# untitled.net
KiCad netlist of a schematic drawn in EAGLE
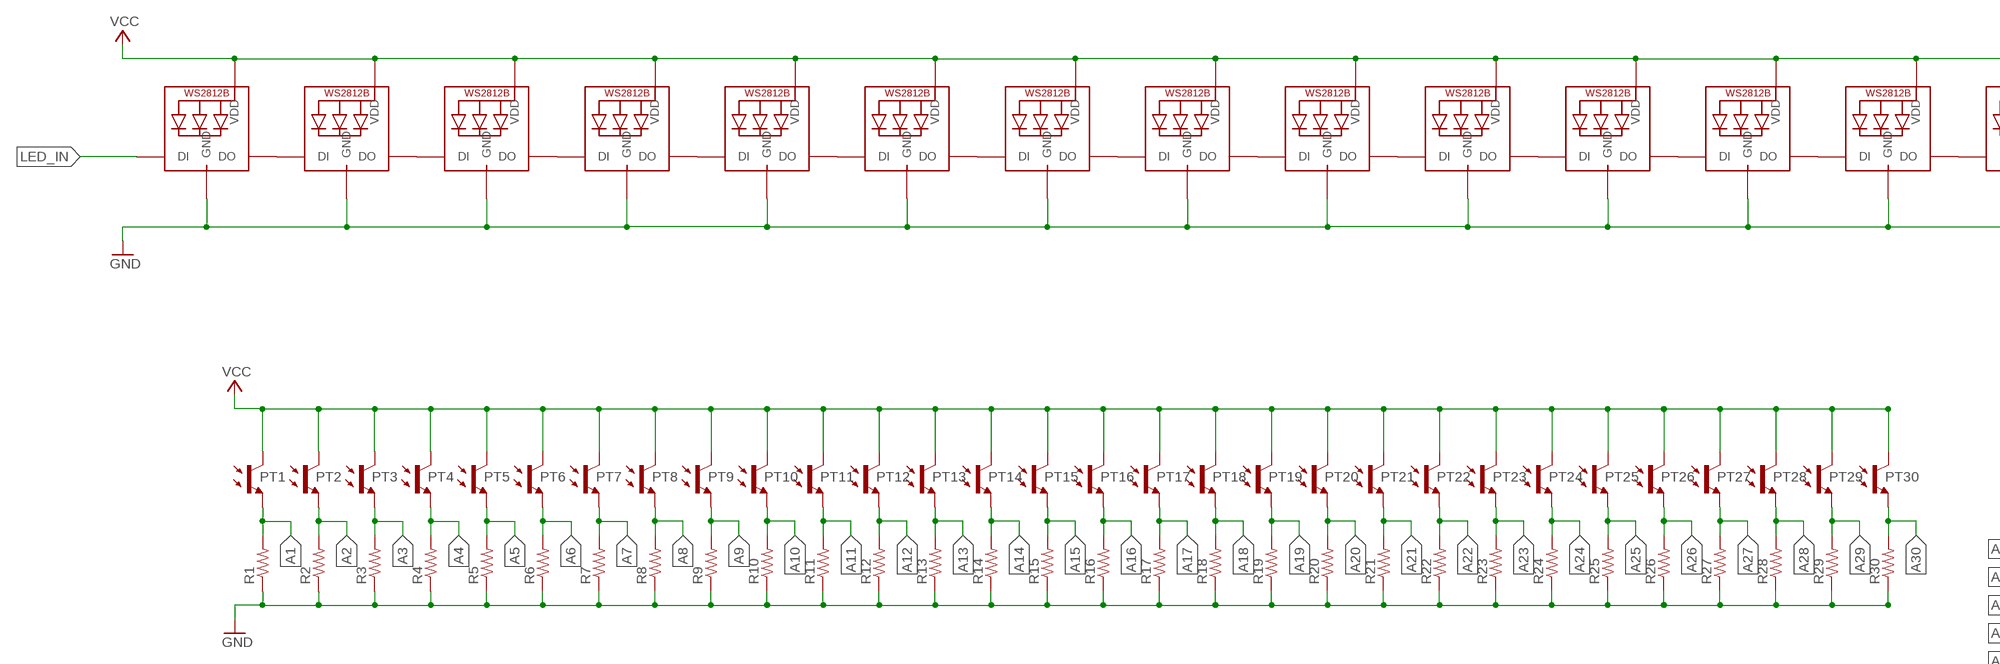
[diagram p0: schematic, sheet 1, part 1 of 2]
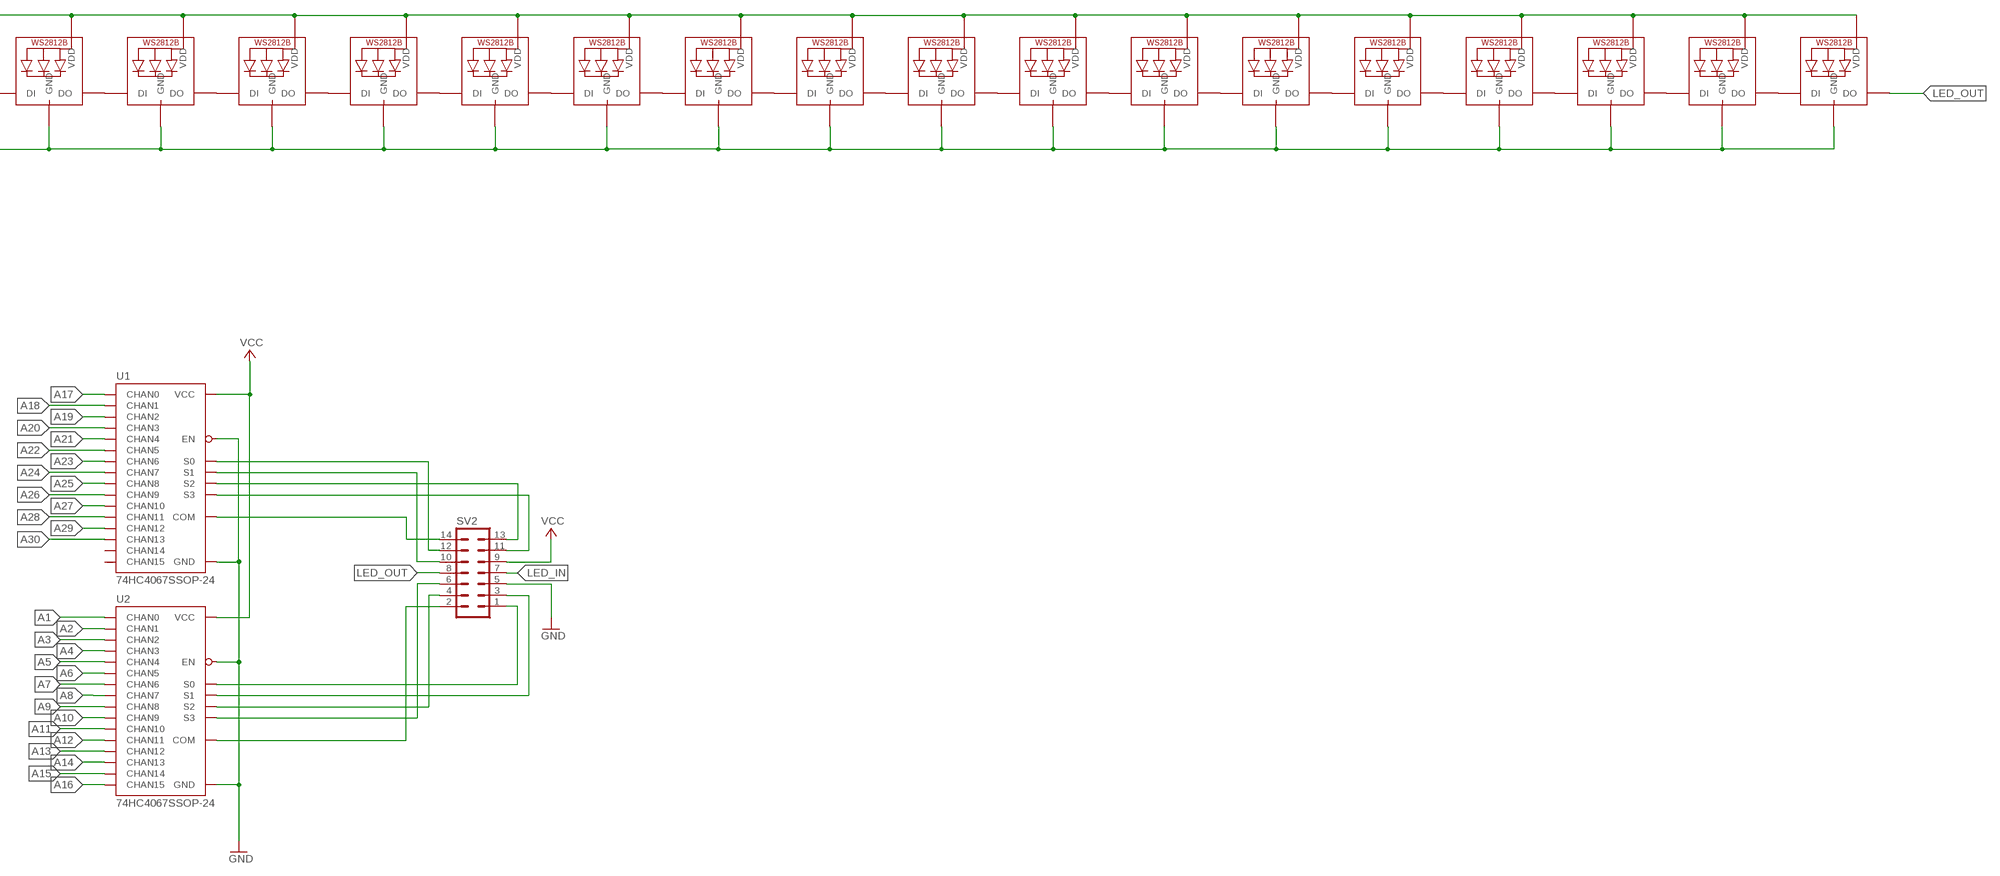
[diagram p1: schematic, sheet 1, part 2 of 2]

(export (version "E")
  (design (tool "Eeschema 10.0.6"))
  (components
    (comp (ref "LED1")
      (value "WS2812B_5050N")
      (footprint "eagle-import:WS2812B-NARROW")
      (libsource (lib "eagle-import") (part "WS2812B_5050N"))
    )
    (comp (ref "LED2")
      (value "WS2812B_5050N")
      (footprint "eagle-import:WS2812B-NARROW")
      (libsource (lib "eagle-import") (part "WS2812B_5050N"))
    )
    (comp (ref "LED3")
      (value "WS2812B_5050N")
      (footprint "eagle-import:WS2812B-NARROW")
      (libsource (lib "eagle-import") (part "WS2812B_5050N"))
    )
    (comp (ref "LED4")
      (value "WS2812B_5050N")
      (footprint "eagle-import:WS2812B-NARROW")
      (libsource (lib "eagle-import") (part "WS2812B_5050N"))
    )
    (comp (ref "LED5")
      (value "WS2812B_5050N")
      (footprint "eagle-import:WS2812B-NARROW")
      (libsource (lib "eagle-import") (part "WS2812B_5050N"))
    )
    (comp (ref "LED6")
      (value "WS2812B_5050N")
      (footprint "eagle-import:WS2812B-NARROW")
      (libsource (lib "eagle-import") (part "WS2812B_5050N"))
    )
    (comp (ref "LED7")
      (value "WS2812B_5050N")
      (footprint "eagle-import:WS2812B-NARROW")
      (libsource (lib "eagle-import") (part "WS2812B_5050N"))
    )
    (comp (ref "LED8")
      (value "WS2812B_5050N")
      (footprint "eagle-import:WS2812B-NARROW")
      (libsource (lib "eagle-import") (part "WS2812B_5050N"))
    )
    (comp (ref "LED9")
      (value "WS2812B_5050N")
      (footprint "eagle-import:WS2812B-NARROW")
      (libsource (lib "eagle-import") (part "WS2812B_5050N"))
    )
    (comp (ref "LED10")
      (value "WS2812B_5050N")
      (footprint "eagle-import:WS2812B-NARROW")
      (libsource (lib "eagle-import") (part "WS2812B_5050N"))
    )
    (comp (ref "LED11")
      (value "WS2812B_5050N")
      (footprint "eagle-import:WS2812B-NARROW")
      (libsource (lib "eagle-import") (part "WS2812B_5050N"))
    )
    (comp (ref "LED12")
      (value "WS2812B_5050N")
      (footprint "eagle-import:WS2812B-NARROW")
      (libsource (lib "eagle-import") (part "WS2812B_5050N"))
    )
    (comp (ref "LED13")
      (value "WS2812B_5050N")
      (footprint "eagle-import:WS2812B-NARROW")
      (libsource (lib "eagle-import") (part "WS2812B_5050N"))
    )
    (comp (ref "LED14")
      (value "WS2812B_5050N")
      (footprint "eagle-import:WS2812B-NARROW")
      (libsource (lib "eagle-import") (part "WS2812B_5050N"))
    )
    (comp (ref "LED15")
      (value "WS2812B_5050N")
      (footprint "eagle-import:WS2812B-NARROW")
      (libsource (lib "eagle-import") (part "WS2812B_5050N"))
    )
    (comp (ref "LED16")
      (value "WS2812B_5050N")
      (footprint "eagle-import:WS2812B-NARROW")
      (libsource (lib "eagle-import") (part "WS2812B_5050N"))
    )
    (comp (ref "LED17")
      (value "WS2812B_5050N")
      (footprint "eagle-import:WS2812B-NARROW")
      (libsource (lib "eagle-import") (part "WS2812B_5050N"))
    )
    (comp (ref "LED18")
      (value "WS2812B_5050N")
      (footprint "eagle-import:WS2812B-NARROW")
      (libsource (lib "eagle-import") (part "WS2812B_5050N"))
    )
    (comp (ref "LED19")
      (value "WS2812B_5050N")
      (footprint "eagle-import:WS2812B-NARROW")
      (libsource (lib "eagle-import") (part "WS2812B_5050N"))
    )
    (comp (ref "LED20")
      (value "WS2812B_5050N")
      (footprint "eagle-import:WS2812B-NARROW")
      (libsource (lib "eagle-import") (part "WS2812B_5050N"))
    )
    (comp (ref "LED21")
      (value "WS2812B_5050N")
      (footprint "eagle-import:WS2812B-NARROW")
      (libsource (lib "eagle-import") (part "WS2812B_5050N"))
    )
    (comp (ref "LED22")
      (value "WS2812B_5050N")
      (footprint "eagle-import:WS2812B-NARROW")
      (libsource (lib "eagle-import") (part "WS2812B_5050N"))
    )
    (comp (ref "LED23")
      (value "WS2812B_5050N")
      (footprint "eagle-import:WS2812B-NARROW")
      (libsource (lib "eagle-import") (part "WS2812B_5050N"))
    )
    (comp (ref "LED24")
      (value "WS2812B_5050N")
      (footprint "eagle-import:WS2812B-NARROW")
      (libsource (lib "eagle-import") (part "WS2812B_5050N"))
    )
    (comp (ref "LED25")
      (value "WS2812B_5050N")
      (footprint "eagle-import:WS2812B-NARROW")
      (libsource (lib "eagle-import") (part "WS2812B_5050N"))
    )
    (comp (ref "LED26")
      (value "WS2812B_5050N")
      (footprint "eagle-import:WS2812B-NARROW")
      (libsource (lib "eagle-import") (part "WS2812B_5050N"))
    )
    (comp (ref "LED27")
      (value "WS2812B_5050N")
      (footprint "eagle-import:WS2812B-NARROW")
      (libsource (lib "eagle-import") (part "WS2812B_5050N"))
    )
    (comp (ref "LED28")
      (value "WS2812B_5050N")
      (footprint "eagle-import:WS2812B-NARROW")
      (libsource (lib "eagle-import") (part "WS2812B_5050N"))
    )
    (comp (ref "LED29")
      (value "WS2812B_5050N")
      (footprint "eagle-import:WS2812B-NARROW")
      (libsource (lib "eagle-import") (part "WS2812B_5050N"))
    )
    (comp (ref "LED30")
      (value "WS2812B_5050N")
      (footprint "eagle-import:WS2812B-NARROW")
      (libsource (lib "eagle-import") (part "WS2812B_5050N"))
    )
    (comp (ref "PT1")
      (value "TPS611")
      (footprint "eagle-import:NJL7502L")
      (libsource (lib "eagle-import") (part "NJL7502L"))
    )
    (comp (ref "PT2")
      (value "TPS611")
      (footprint "eagle-import:NJL7502L")
      (libsource (lib "eagle-import") (part "NJL7502L"))
    )
    (comp (ref "PT3")
      (value "TPS611")
      (footprint "eagle-import:NJL7502L")
      (libsource (lib "eagle-import") (part "NJL7502L"))
    )
    (comp (ref "PT4")
      (value "TPS611")
      (footprint "eagle-import:NJL7502L")
      (libsource (lib "eagle-import") (part "NJL7502L"))
    )
    (comp (ref "PT5")
      (value "TPS611")
      (footprint "eagle-import:NJL7502L")
      (libsource (lib "eagle-import") (part "NJL7502L"))
    )
    (comp (ref "PT6")
      (value "TPS611")
      (footprint "eagle-import:NJL7502L")
      (libsource (lib "eagle-import") (part "NJL7502L"))
    )
    (comp (ref "PT7")
      (value "TPS611")
      (footprint "eagle-import:NJL7502L")
      (libsource (lib "eagle-import") (part "NJL7502L"))
    )
    (comp (ref "PT8")
      (value "TPS611")
      (footprint "eagle-import:NJL7502L")
      (libsource (lib "eagle-import") (part "NJL7502L"))
    )
    (comp (ref "PT9")
      (value "TPS611")
      (footprint "eagle-import:NJL7502L")
      (libsource (lib "eagle-import") (part "NJL7502L"))
    )
    (comp (ref "PT10")
      (value "TPS611")
      (footprint "eagle-import:NJL7502L")
      (libsource (lib "eagle-import") (part "NJL7502L"))
    )
    (comp (ref "PT11")
      (value "TPS611")
      (footprint "eagle-import:NJL7502L")
      (libsource (lib "eagle-import") (part "NJL7502L"))
    )
    (comp (ref "PT12")
      (value "TPS611")
      (footprint "eagle-import:NJL7502L")
      (libsource (lib "eagle-import") (part "NJL7502L"))
    )
    (comp (ref "PT13")
      (value "TPS611")
      (footprint "eagle-import:NJL7502L")
      (libsource (lib "eagle-import") (part "NJL7502L"))
    )
    (comp (ref "PT14")
      (value "TPS611")
      (footprint "eagle-import:NJL7502L")
      (libsource (lib "eagle-import") (part "NJL7502L"))
    )
    (comp (ref "PT15")
      (value "TPS611")
      (footprint "eagle-import:NJL7502L")
      (libsource (lib "eagle-import") (part "NJL7502L"))
    )
    (comp (ref "PT16")
      (value "TPS611")
      (footprint "eagle-import:NJL7502L")
      (libsource (lib "eagle-import") (part "NJL7502L"))
    )
    (comp (ref "PT17")
      (value "TPS611")
      (footprint "eagle-import:NJL7502L")
      (libsource (lib "eagle-import") (part "NJL7502L"))
    )
    (comp (ref "PT18")
      (value "TPS611")
      (footprint "eagle-import:NJL7502L")
      (libsource (lib "eagle-import") (part "NJL7502L"))
    )
    (comp (ref "PT19")
      (value "TPS611")
      (footprint "eagle-import:NJL7502L")
      (libsource (lib "eagle-import") (part "NJL7502L"))
    )
    (comp (ref "PT20")
      (value "TPS611")
      (footprint "eagle-import:NJL7502L")
      (libsource (lib "eagle-import") (part "NJL7502L"))
    )
    (comp (ref "PT21")
      (value "TPS611")
      (footprint "eagle-import:NJL7502L")
      (libsource (lib "eagle-import") (part "NJL7502L"))
    )
    (comp (ref "PT22")
      (value "TPS611")
      (footprint "eagle-import:NJL7502L")
      (libsource (lib "eagle-import") (part "NJL7502L"))
    )
    (comp (ref "PT23")
      (value "TPS611")
      (footprint "eagle-import:NJL7502L")
      (libsource (lib "eagle-import") (part "NJL7502L"))
    )
    (comp (ref "PT24")
      (value "TPS611")
      (footprint "eagle-import:NJL7502L")
      (libsource (lib "eagle-import") (part "NJL7502L"))
    )
    (comp (ref "PT25")
      (value "TPS611")
      (footprint "eagle-import:NJL7502L")
      (libsource (lib "eagle-import") (part "NJL7502L"))
    )
    (comp (ref "PT26")
      (value "TPS611")
      (footprint "eagle-import:NJL7502L")
      (libsource (lib "eagle-import") (part "NJL7502L"))
    )
    (comp (ref "PT27")
      (value "TPS611")
      (footprint "eagle-import:NJL7502L")
      (libsource (lib "eagle-import") (part "NJL7502L"))
    )
    (comp (ref "PT28")
      (value "TPS611")
      (footprint "eagle-import:NJL7502L")
      (libsource (lib "eagle-import") (part "NJL7502L"))
    )
    (comp (ref "PT29")
      (value "TPS611")
      (footprint "eagle-import:NJL7502L")
      (libsource (lib "eagle-import") (part "NJL7502L"))
    )
    (comp (ref "PT30")
      (value "TPS611")
      (footprint "eagle-import:NJL7502L")
      (libsource (lib "eagle-import") (part "NJL7502L"))
    )
    (comp (ref "R1")
      (value "R-US_M2012")
      (footprint "eagle-import:M2012")
      (libsource (lib "eagle-import") (part "R-US_M2012"))
    )
    (comp (ref "R2")
      (value "R-US_M2012")
      (footprint "eagle-import:M2012")
      (libsource (lib "eagle-import") (part "R-US_M2012"))
    )
    (comp (ref "R3")
      (value "R-US_M2012")
      (footprint "eagle-import:M2012")
      (libsource (lib "eagle-import") (part "R-US_M2012"))
    )
    (comp (ref "R4")
      (value "R-US_M2012")
      (footprint "eagle-import:M2012")
      (libsource (lib "eagle-import") (part "R-US_M2012"))
    )
    (comp (ref "R5")
      (value "R-US_M2012")
      (footprint "eagle-import:M2012")
      (libsource (lib "eagle-import") (part "R-US_M2012"))
    )
    (comp (ref "R6")
      (value "R-US_M2012")
      (footprint "eagle-import:M2012")
      (libsource (lib "eagle-import") (part "R-US_M2012"))
    )
    (comp (ref "R7")
      (value "R-US_M2012")
      (footprint "eagle-import:M2012")
      (libsource (lib "eagle-import") (part "R-US_M2012"))
    )
    (comp (ref "R8")
      (value "R-US_M2012")
      (footprint "eagle-import:M2012")
      (libsource (lib "eagle-import") (part "R-US_M2012"))
    )
    (comp (ref "R9")
      (value "R-US_M2012")
      (footprint "eagle-import:M2012")
      (libsource (lib "eagle-import") (part "R-US_M2012"))
    )
    (comp (ref "R10")
      (value "R-US_M2012")
      (footprint "eagle-import:M2012")
      (libsource (lib "eagle-import") (part "R-US_M2012"))
    )
    (comp (ref "R11")
      (value "R-US_M2012")
      (footprint "eagle-import:M2012")
      (libsource (lib "eagle-import") (part "R-US_M2012"))
    )
    (comp (ref "R12")
      (value "R-US_M2012")
      (footprint "eagle-import:M2012")
      (libsource (lib "eagle-import") (part "R-US_M2012"))
    )
    (comp (ref "R13")
      (value "R-US_M2012")
      (footprint "eagle-import:M2012")
      (libsource (lib "eagle-import") (part "R-US_M2012"))
    )
    (comp (ref "R14")
      (value "R-US_M2012")
      (footprint "eagle-import:M2012")
      (libsource (lib "eagle-import") (part "R-US_M2012"))
    )
    (comp (ref "R15")
      (value "R-US_M2012")
      (footprint "eagle-import:M2012")
      (libsource (lib "eagle-import") (part "R-US_M2012"))
    )
    (comp (ref "R16")
      (value "R-US_M2012")
      (footprint "eagle-import:M2012")
      (libsource (lib "eagle-import") (part "R-US_M2012"))
    )
    (comp (ref "R17")
      (value "R-US_M2012")
      (footprint "eagle-import:M2012")
      (libsource (lib "eagle-import") (part "R-US_M2012"))
    )
    (comp (ref "R18")
      (value "R-US_M2012")
      (footprint "eagle-import:M2012")
      (libsource (lib "eagle-import") (part "R-US_M2012"))
    )
    (comp (ref "R19")
      (value "R-US_M2012")
      (footprint "eagle-import:M2012")
      (libsource (lib "eagle-import") (part "R-US_M2012"))
    )
    (comp (ref "R20")
      (value "R-US_M2012")
      (footprint "eagle-import:M2012")
      (libsource (lib "eagle-import") (part "R-US_M2012"))
    )
    (comp (ref "R21")
      (value "R-US_M2012")
      (footprint "eagle-import:M2012")
      (libsource (lib "eagle-import") (part "R-US_M2012"))
    )
    (comp (ref "R22")
      (value "R-US_M2012")
      (footprint "eagle-import:M2012")
      (libsource (lib "eagle-import") (part "R-US_M2012"))
    )
    (comp (ref "R23")
      (value "R-US_M2012")
      (footprint "eagle-import:M2012")
      (libsource (lib "eagle-import") (part "R-US_M2012"))
    )
    (comp (ref "R24")
      (value "R-US_M2012")
      (footprint "eagle-import:M2012")
      (libsource (lib "eagle-import") (part "R-US_M2012"))
    )
    (comp (ref "R25")
      (value "R-US_M2012")
      (footprint "eagle-import:M2012")
      (libsource (lib "eagle-import") (part "R-US_M2012"))
    )
    (comp (ref "R26")
      (value "R-US_M2012")
      (footprint "eagle-import:M2012")
      (libsource (lib "eagle-import") (part "R-US_M2012"))
    )
    (comp (ref "R27")
      (value "R-US_M2012")
      (footprint "eagle-import:M2012")
      (libsource (lib "eagle-import") (part "R-US_M2012"))
    )
    (comp (ref "R28")
      (value "R-US_M2012")
      (footprint "eagle-import:M2012")
      (libsource (lib "eagle-import") (part "R-US_M2012"))
    )
    (comp (ref "R29")
      (value "R-US_M2012")
      (footprint "eagle-import:M2012")
      (libsource (lib "eagle-import") (part "R-US_M2012"))
    )
    (comp (ref "R30")
      (value "R-US_M2012")
      (footprint "eagle-import:M2012")
      (libsource (lib "eagle-import") (part "R-US_M2012"))
    )
    (comp (ref "SV2")
      (value "MA07-2")
      (footprint "eagle-import:MA07-2")
      (libsource (lib "eagle-import") (part "MA07-2"))
    )
    (comp (ref "U1")
      (value "74HC4067SSOP-24")
      (footprint "eagle-import:SSOP24")
      (fields (field (name "MF") "Nexperia") (field (name "MP") "74HC4067"))
      (libsource (lib "eagle-import") (part "74HC4067SSOP-24"))
    )
    (comp (ref "U2")
      (value "74HC4067SSOP-24")
      (footprint "eagle-import:SSOP24")
      (fields (field (name "MF") "Nexperia") (field (name "MP") "74HC4067"))
      (libsource (lib "eagle-import") (part "74HC4067SSOP-24"))
    )
  )
  (nets
    (net (code "1") (name "A1") (class "Default")
      (node (ref "PT1") (pin "E") (pinfunction "E_E") (pintype "passive"))
      (node (ref "R1") (pin "2") (pinfunction "2_2") (pintype "passive"))
      (node (ref "U2") (pin "9") (pinfunction "CHAN0_9") (pintype "bidirectional"))
    )
    (net (code "2") (name "A2") (class "Default")
      (node (ref "PT2") (pin "E") (pinfunction "E_E") (pintype "passive"))
      (node (ref "R2") (pin "2") (pinfunction "2_2") (pintype "passive"))
      (node (ref "U2") (pin "8") (pinfunction "CHAN1_8") (pintype "bidirectional"))
    )
    (net (code "3") (name "A3") (class "Default")
      (node (ref "PT3") (pin "E") (pinfunction "E_E") (pintype "passive"))
      (node (ref "R3") (pin "2") (pinfunction "2_2") (pintype "passive"))
      (node (ref "U2") (pin "7") (pinfunction "CHAN2_7") (pintype "bidirectional"))
    )
    (net (code "4") (name "A4") (class "Default")
      (node (ref "PT4") (pin "E") (pinfunction "E_E") (pintype "passive"))
      (node (ref "R4") (pin "2") (pinfunction "2_2") (pintype "passive"))
      (node (ref "U2") (pin "6") (pinfunction "CHAN3_6") (pintype "bidirectional"))
    )
    (net (code "5") (name "A5") (class "Default")
      (node (ref "PT5") (pin "E") (pinfunction "E_E") (pintype "passive"))
      (node (ref "R5") (pin "2") (pinfunction "2_2") (pintype "passive"))
      (node (ref "U2") (pin "5") (pinfunction "CHAN4_5") (pintype "bidirectional"))
    )
    (net (code "6") (name "A6") (class "Default")
      (node (ref "PT6") (pin "E") (pinfunction "E_E") (pintype "passive"))
      (node (ref "R6") (pin "2") (pinfunction "2_2") (pintype "passive"))
      (node (ref "U2") (pin "4") (pinfunction "CHAN5_4") (pintype "bidirectional"))
    )
    (net (code "7") (name "A7") (class "Default")
      (node (ref "PT7") (pin "E") (pinfunction "E_E") (pintype "passive"))
      (node (ref "R7") (pin "2") (pinfunction "2_2") (pintype "passive"))
      (node (ref "U2") (pin "3") (pinfunction "CHAN6_3") (pintype "bidirectional"))
    )
    (net (code "8") (name "A8") (class "Default")
      (node (ref "PT8") (pin "E") (pinfunction "E_E") (pintype "passive"))
      (node (ref "R8") (pin "2") (pinfunction "2_2") (pintype "passive"))
      (node (ref "U2") (pin "2") (pinfunction "CHAN7_2") (pintype "bidirectional"))
    )
    (net (code "9") (name "A9") (class "Default")
      (node (ref "PT9") (pin "E") (pinfunction "E_E") (pintype "passive"))
      (node (ref "R9") (pin "2") (pinfunction "2_2") (pintype "passive"))
      (node (ref "U2") (pin "23") (pinfunction "CHAN8_23") (pintype "bidirectional"))
    )
    (net (code "10") (name "A10") (class "Default")
      (node (ref "PT10") (pin "E") (pinfunction "E_E") (pintype "passive"))
      (node (ref "R10") (pin "2") (pinfunction "2_2") (pintype "passive"))
      (node (ref "U2") (pin "22") (pinfunction "CHAN9_22") (pintype "bidirectional"))
    )
    (net (code "11") (name "A11") (class "Default")
      (node (ref "PT11") (pin "E") (pinfunction "E_E") (pintype "passive"))
      (node (ref "R11") (pin "2") (pinfunction "2_2") (pintype "passive"))
      (node (ref "U2") (pin "21") (pinfunction "CHAN10_21") (pintype "bidirectional"))
    )
    (net (code "12") (name "A12") (class "Default")
      (node (ref "PT12") (pin "E") (pinfunction "E_E") (pintype "passive"))
      (node (ref "R12") (pin "2") (pinfunction "2_2") (pintype "passive"))
      (node (ref "U2") (pin "20") (pinfunction "CHAN11_20") (pintype "bidirectional"))
    )
    (net (code "13") (name "A13") (class "Default")
      (node (ref "PT13") (pin "E") (pinfunction "E_E") (pintype "passive"))
      (node (ref "R13") (pin "2") (pinfunction "2_2") (pintype "passive"))
      (node (ref "U2") (pin "19") (pinfunction "CHAN12_19") (pintype "bidirectional"))
    )
    (net (code "14") (name "A14") (class "Default")
      (node (ref "PT14") (pin "E") (pinfunction "E_E") (pintype "passive"))
      (node (ref "R14") (pin "2") (pinfunction "2_2") (pintype "passive"))
      (node (ref "U2") (pin "18") (pinfunction "CHAN13_18") (pintype "bidirectional"))
    )
    (net (code "15") (name "A15") (class "Default")
      (node (ref "PT15") (pin "E") (pinfunction "E_E") (pintype "passive"))
      (node (ref "R15") (pin "2") (pinfunction "2_2") (pintype "passive"))
      (node (ref "U2") (pin "17") (pinfunction "CHAN14_17") (pintype "bidirectional"))
    )
    (net (code "16") (name "A16") (class "Default")
      (node (ref "PT16") (pin "E") (pinfunction "E_E") (pintype "passive"))
      (node (ref "R16") (pin "2") (pinfunction "2_2") (pintype "passive"))
      (node (ref "U2") (pin "16") (pinfunction "CHAN15_16") (pintype "bidirectional"))
    )
    (net (code "17") (name "A17") (class "Default")
      (node (ref "PT17") (pin "E") (pinfunction "E_E") (pintype "passive"))
      (node (ref "R17") (pin "2") (pinfunction "2_2") (pintype "passive"))
      (node (ref "U1") (pin "9") (pinfunction "CHAN0_9") (pintype "bidirectional"))
    )
    (net (code "18") (name "A18") (class "Default")
      (node (ref "PT18") (pin "E") (pinfunction "E_E") (pintype "passive"))
      (node (ref "R18") (pin "2") (pinfunction "2_2") (pintype "passive"))
      (node (ref "U1") (pin "8") (pinfunction "CHAN1_8") (pintype "bidirectional"))
    )
    (net (code "19") (name "A19") (class "Default")
      (node (ref "PT19") (pin "E") (pinfunction "E_E") (pintype "passive"))
      (node (ref "R19") (pin "2") (pinfunction "2_2") (pintype "passive"))
      (node (ref "U1") (pin "7") (pinfunction "CHAN2_7") (pintype "bidirectional"))
    )
    (net (code "20") (name "A20") (class "Default")
      (node (ref "PT20") (pin "E") (pinfunction "E_E") (pintype "passive"))
      (node (ref "R20") (pin "2") (pinfunction "2_2") (pintype "passive"))
      (node (ref "U1") (pin "6") (pinfunction "CHAN3_6") (pintype "bidirectional"))
    )
    (net (code "21") (name "A21") (class "Default")
      (node (ref "PT21") (pin "E") (pinfunction "E_E") (pintype "passive"))
      (node (ref "R21") (pin "2") (pinfunction "2_2") (pintype "passive"))
      (node (ref "U1") (pin "5") (pinfunction "CHAN4_5") (pintype "bidirectional"))
    )
    (net (code "22") (name "A22") (class "Default")
      (node (ref "PT22") (pin "E") (pinfunction "E_E") (pintype "passive"))
      (node (ref "R22") (pin "2") (pinfunction "2_2") (pintype "passive"))
      (node (ref "U1") (pin "4") (pinfunction "CHAN5_4") (pintype "bidirectional"))
    )
    (net (code "23") (name "A23") (class "Default")
      (node (ref "PT23") (pin "E") (pinfunction "E_E") (pintype "passive"))
      (node (ref "R23") (pin "2") (pinfunction "2_2") (pintype "passive"))
      (node (ref "U1") (pin "3") (pinfunction "CHAN6_3") (pintype "bidirectional"))
    )
    (net (code "24") (name "A24") (class "Default")
      (node (ref "PT24") (pin "E") (pinfunction "E_E") (pintype "passive"))
      (node (ref "R24") (pin "2") (pinfunction "2_2") (pintype "passive"))
      (node (ref "U1") (pin "2") (pinfunction "CHAN7_2") (pintype "bidirectional"))
    )
    (net (code "25") (name "A25") (class "Default")
      (node (ref "PT25") (pin "E") (pinfunction "E_E") (pintype "passive"))
      (node (ref "R25") (pin "2") (pinfunction "2_2") (pintype "passive"))
      (node (ref "U1") (pin "23") (pinfunction "CHAN8_23") (pintype "bidirectional"))
    )
    (net (code "26") (name "A26") (class "Default")
      (node (ref "PT26") (pin "E") (pinfunction "E_E") (pintype "passive"))
      (node (ref "R26") (pin "2") (pinfunction "2_2") (pintype "passive"))
      (node (ref "U1") (pin "22") (pinfunction "CHAN9_22") (pintype "bidirectional"))
    )
    (net (code "27") (name "A27") (class "Default")
      (node (ref "PT27") (pin "E") (pinfunction "E_E") (pintype "passive"))
      (node (ref "R27") (pin "2") (pinfunction "2_2") (pintype "passive"))
      (node (ref "U1") (pin "21") (pinfunction "CHAN10_21") (pintype "bidirectional"))
    )
    (net (code "28") (name "A28") (class "Default")
      (node (ref "PT28") (pin "E") (pinfunction "E_E") (pintype "passive"))
      (node (ref "R28") (pin "2") (pinfunction "2_2") (pintype "passive"))
      (node (ref "U1") (pin "20") (pinfunction "CHAN11_20") (pintype "bidirectional"))
    )
    (net (code "29") (name "A29") (class "Default")
      (node (ref "PT29") (pin "E") (pinfunction "E_E") (pintype "passive"))
      (node (ref "R29") (pin "2") (pinfunction "2_2") (pintype "passive"))
      (node (ref "U1") (pin "19") (pinfunction "CHAN12_19") (pintype "bidirectional"))
    )
    (net (code "30") (name "A30") (class "Default")
      (node (ref "PT30") (pin "E") (pinfunction "E_E") (pintype "passive"))
      (node (ref "R30") (pin "2") (pinfunction "2_2") (pintype "passive"))
      (node (ref "U1") (pin "18") (pinfunction "CHAN13_18") (pintype "bidirectional"))
    )
    (net (code "31") (name "GND") (class "Default")
      (node (ref "LED1") (pin "3-GND") (pinfunction "GND_3-GND") (pintype "power_in"))
      (node (ref "LED10") (pin "3-GND") (pinfunction "GND_3-GND") (pintype "power_in"))
      (node (ref "LED11") (pin "3-GND") (pinfunction "GND_3-GND") (pintype "power_in"))
      (node (ref "LED12") (pin "3-GND") (pinfunction "GND_3-GND") (pintype "power_in"))
      (node (ref "LED13") (pin "3-GND") (pinfunction "GND_3-GND") (pintype "power_in"))
      (node (ref "LED14") (pin "3-GND") (pinfunction "GND_3-GND") (pintype "power_in"))
      (node (ref "LED15") (pin "3-GND") (pinfunction "GND_3-GND") (pintype "power_in"))
      (node (ref "LED16") (pin "3-GND") (pinfunction "GND_3-GND") (pintype "power_in"))
      (node (ref "LED17") (pin "3-GND") (pinfunction "GND_3-GND") (pintype "power_in"))
      (node (ref "LED18") (pin "3-GND") (pinfunction "GND_3-GND") (pintype "power_in"))
      (node (ref "LED19") (pin "3-GND") (pinfunction "GND_3-GND") (pintype "power_in"))
      (node (ref "LED2") (pin "3-GND") (pinfunction "GND_3-GND") (pintype "power_in"))
      (node (ref "LED20") (pin "3-GND") (pinfunction "GND_3-GND") (pintype "power_in"))
      (node (ref "LED21") (pin "3-GND") (pinfunction "GND_3-GND") (pintype "power_in"))
      (node (ref "LED22") (pin "3-GND") (pinfunction "GND_3-GND") (pintype "power_in"))
      (node (ref "LED23") (pin "3-GND") (pinfunction "GND_3-GND") (pintype "power_in"))
      (node (ref "LED24") (pin "3-GND") (pinfunction "GND_3-GND") (pintype "power_in"))
      (node (ref "LED25") (pin "3-GND") (pinfunction "GND_3-GND") (pintype "power_in"))
      (node (ref "LED26") (pin "3-GND") (pinfunction "GND_3-GND") (pintype "power_in"))
      (node (ref "LED27") (pin "3-GND") (pinfunction "GND_3-GND") (pintype "power_in"))
      (node (ref "LED28") (pin "3-GND") (pinfunction "GND_3-GND") (pintype "power_in"))
      (node (ref "LED29") (pin "3-GND") (pinfunction "GND_3-GND") (pintype "power_in"))
      (node (ref "LED3") (pin "3-GND") (pinfunction "GND_3-GND") (pintype "power_in"))
      (node (ref "LED30") (pin "3-GND") (pinfunction "GND_3-GND") (pintype "power_in"))
      (node (ref "LED4") (pin "3-GND") (pinfunction "GND_3-GND") (pintype "power_in"))
      (node (ref "LED5") (pin "3-GND") (pinfunction "GND_3-GND") (pintype "power_in"))
      (node (ref "LED6") (pin "3-GND") (pinfunction "GND_3-GND") (pintype "power_in"))
      (node (ref "LED7") (pin "3-GND") (pinfunction "GND_3-GND") (pintype "power_in"))
      (node (ref "LED8") (pin "3-GND") (pinfunction "GND_3-GND") (pintype "power_in"))
      (node (ref "LED9") (pin "3-GND") (pinfunction "GND_3-GND") (pintype "power_in"))
      (node (ref "R1") (pin "1") (pinfunction "1_1") (pintype "passive"))
      (node (ref "R10") (pin "1") (pinfunction "1_1") (pintype "passive"))
      (node (ref "R11") (pin "1") (pinfunction "1_1") (pintype "passive"))
      (node (ref "R12") (pin "1") (pinfunction "1_1") (pintype "passive"))
      (node (ref "R13") (pin "1") (pinfunction "1_1") (pintype "passive"))
      (node (ref "R14") (pin "1") (pinfunction "1_1") (pintype "passive"))
      (node (ref "R15") (pin "1") (pinfunction "1_1") (pintype "passive"))
      (node (ref "R16") (pin "1") (pinfunction "1_1") (pintype "passive"))
      (node (ref "R17") (pin "1") (pinfunction "1_1") (pintype "passive"))
      (node (ref "R18") (pin "1") (pinfunction "1_1") (pintype "passive"))
      (node (ref "R19") (pin "1") (pinfunction "1_1") (pintype "passive"))
      (node (ref "R2") (pin "1") (pinfunction "1_1") (pintype "passive"))
      (node (ref "R20") (pin "1") (pinfunction "1_1") (pintype "passive"))
      (node (ref "R21") (pin "1") (pinfunction "1_1") (pintype "passive"))
      (node (ref "R22") (pin "1") (pinfunction "1_1") (pintype "passive"))
      (node (ref "R23") (pin "1") (pinfunction "1_1") (pintype "passive"))
      (node (ref "R24") (pin "1") (pinfunction "1_1") (pintype "passive"))
      (node (ref "R25") (pin "1") (pinfunction "1_1") (pintype "passive"))
      (node (ref "R26") (pin "1") (pinfunction "1_1") (pintype "passive"))
      (node (ref "R27") (pin "1") (pinfunction "1_1") (pintype "passive"))
      (node (ref "R28") (pin "1") (pinfunction "1_1") (pintype "passive"))
      (node (ref "R29") (pin "1") (pinfunction "1_1") (pintype "passive"))
      (node (ref "R3") (pin "1") (pinfunction "1_1") (pintype "passive"))
      (node (ref "R30") (pin "1") (pinfunction "1_1") (pintype "passive"))
      (node (ref "R4") (pin "1") (pinfunction "1_1") (pintype "passive"))
      (node (ref "R5") (pin "1") (pinfunction "1_1") (pintype "passive"))
      (node (ref "R6") (pin "1") (pinfunction "1_1") (pintype "passive"))
      (node (ref "R7") (pin "1") (pinfunction "1_1") (pintype "passive"))
      (node (ref "R8") (pin "1") (pinfunction "1_1") (pintype "passive"))
      (node (ref "R9") (pin "1") (pinfunction "1_1") (pintype "passive"))
      (node (ref "SV2") (pin "5") (pinfunction "5_5") (pintype "passive"))
      (node (ref "U1") (pin "12") (pinfunction "GND_12") (pintype "bidirectional"))
      (node (ref "U1") (pin "15") (pinfunction "EN_15") (pintype "input"))
      (node (ref "U2") (pin "12") (pinfunction "GND_12") (pintype "bidirectional"))
      (node (ref "U2") (pin "15") (pinfunction "EN_15") (pintype "input"))
    )
    (net (code "32") (name "LED_IN") (class "Default")
      (node (ref "LED1") (pin "4-DIN") (pinfunction "DI_4-DIN") (pintype "input"))
      (node (ref "SV2") (pin "7") (pinfunction "7_7") (pintype "passive"))
    )
    (net (code "33") (name "LED_OUT") (class "Default")
      (node (ref "LED30") (pin "2-DOUT") (pinfunction "DO_2-DOUT") (pintype "output"))
      (node (ref "SV2") (pin "8") (pinfunction "8_8") (pintype "passive"))
    )
    (net (code "34") (name "Net-(LED1-DO)") (class "Default")
      (node (ref "LED1") (pin "2-DOUT") (pinfunction "DO_2-DOUT") (pintype "output"))
      (node (ref "LED2") (pin "4-DIN") (pinfunction "DI_4-DIN") (pintype "input"))
    )
    (net (code "35") (name "Net-(LED2-DO)") (class "Default")
      (node (ref "LED2") (pin "2-DOUT") (pinfunction "DO_2-DOUT") (pintype "output"))
      (node (ref "LED3") (pin "4-DIN") (pinfunction "DI_4-DIN") (pintype "input"))
    )
    (net (code "36") (name "Net-(LED3-DO)") (class "Default")
      (node (ref "LED3") (pin "2-DOUT") (pinfunction "DO_2-DOUT") (pintype "output"))
      (node (ref "LED4") (pin "4-DIN") (pinfunction "DI_4-DIN") (pintype "input"))
    )
    (net (code "37") (name "Net-(LED4-DO)") (class "Default")
      (node (ref "LED4") (pin "2-DOUT") (pinfunction "DO_2-DOUT") (pintype "output"))
      (node (ref "LED5") (pin "4-DIN") (pinfunction "DI_4-DIN") (pintype "input"))
    )
    (net (code "38") (name "Net-(LED5-DO)") (class "Default")
      (node (ref "LED5") (pin "2-DOUT") (pinfunction "DO_2-DOUT") (pintype "output"))
      (node (ref "LED6") (pin "4-DIN") (pinfunction "DI_4-DIN") (pintype "input"))
    )
    (net (code "39") (name "Net-(LED6-DO)") (class "Default")
      (node (ref "LED6") (pin "2-DOUT") (pinfunction "DO_2-DOUT") (pintype "output"))
      (node (ref "LED7") (pin "4-DIN") (pinfunction "DI_4-DIN") (pintype "input"))
    )
    (net (code "40") (name "Net-(LED7-DO)") (class "Default")
      (node (ref "LED7") (pin "2-DOUT") (pinfunction "DO_2-DOUT") (pintype "output"))
      (node (ref "LED8") (pin "4-DIN") (pinfunction "DI_4-DIN") (pintype "input"))
    )
    (net (code "41") (name "Net-(LED8-DO)") (class "Default")
      (node (ref "LED8") (pin "2-DOUT") (pinfunction "DO_2-DOUT") (pintype "output"))
      (node (ref "LED9") (pin "4-DIN") (pinfunction "DI_4-DIN") (pintype "input"))
    )
    (net (code "42") (name "Net-(LED10-DI)") (class "Default")
      (node (ref "LED10") (pin "4-DIN") (pinfunction "DI_4-DIN") (pintype "input"))
      (node (ref "LED9") (pin "2-DOUT") (pinfunction "DO_2-DOUT") (pintype "output"))
    )
    (net (code "43") (name "Net-(LED10-DO)") (class "Default")
      (node (ref "LED10") (pin "2-DOUT") (pinfunction "DO_2-DOUT") (pintype "output"))
      (node (ref "LED11") (pin "4-DIN") (pinfunction "DI_4-DIN") (pintype "input"))
    )
    (net (code "44") (name "Net-(LED11-DO)") (class "Default")
      (node (ref "LED11") (pin "2-DOUT") (pinfunction "DO_2-DOUT") (pintype "output"))
      (node (ref "LED12") (pin "4-DIN") (pinfunction "DI_4-DIN") (pintype "input"))
    )
    (net (code "45") (name "Net-(LED12-DO)") (class "Default")
      (node (ref "LED12") (pin "2-DOUT") (pinfunction "DO_2-DOUT") (pintype "output"))
      (node (ref "LED13") (pin "4-DIN") (pinfunction "DI_4-DIN") (pintype "input"))
    )
    (net (code "46") (name "Net-(LED13-DO)") (class "Default")
      (node (ref "LED13") (pin "2-DOUT") (pinfunction "DO_2-DOUT") (pintype "output"))
      (node (ref "LED14") (pin "4-DIN") (pinfunction "DI_4-DIN") (pintype "input"))
    )
    (net (code "47") (name "Net-(LED14-DO)") (class "Default")
      (node (ref "LED14") (pin "2-DOUT") (pinfunction "DO_2-DOUT") (pintype "output"))
      (node (ref "LED15") (pin "4-DIN") (pinfunction "DI_4-DIN") (pintype "input"))
    )
    (net (code "48") (name "Net-(LED15-DO)") (class "Default")
      (node (ref "LED15") (pin "2-DOUT") (pinfunction "DO_2-DOUT") (pintype "output"))
      (node (ref "LED16") (pin "4-DIN") (pinfunction "DI_4-DIN") (pintype "input"))
    )
    (net (code "49") (name "Net-(LED16-DO)") (class "Default")
      (node (ref "LED16") (pin "2-DOUT") (pinfunction "DO_2-DOUT") (pintype "output"))
      (node (ref "LED17") (pin "4-DIN") (pinfunction "DI_4-DIN") (pintype "input"))
    )
    (net (code "50") (name "Net-(LED17-DO)") (class "Default")
      (node (ref "LED17") (pin "2-DOUT") (pinfunction "DO_2-DOUT") (pintype "output"))
      (node (ref "LED18") (pin "4-DIN") (pinfunction "DI_4-DIN") (pintype "input"))
    )
    (net (code "51") (name "Net-(LED18-DO)") (class "Default")
      (node (ref "LED18") (pin "2-DOUT") (pinfunction "DO_2-DOUT") (pintype "output"))
      (node (ref "LED19") (pin "4-DIN") (pinfunction "DI_4-DIN") (pintype "input"))
    )
    (net (code "52") (name "Net-(LED19-DO)") (class "Default")
      (node (ref "LED19") (pin "2-DOUT") (pinfunction "DO_2-DOUT") (pintype "output"))
      (node (ref "LED20") (pin "4-DIN") (pinfunction "DI_4-DIN") (pintype "input"))
    )
    (net (code "53") (name "Net-(LED20-DO)") (class "Default")
      (node (ref "LED20") (pin "2-DOUT") (pinfunction "DO_2-DOUT") (pintype "output"))
      (node (ref "LED21") (pin "4-DIN") (pinfunction "DI_4-DIN") (pintype "input"))
    )
    (net (code "54") (name "Net-(LED21-DO)") (class "Default")
      (node (ref "LED21") (pin "2-DOUT") (pinfunction "DO_2-DOUT") (pintype "output"))
      (node (ref "LED22") (pin "4-DIN") (pinfunction "DI_4-DIN") (pintype "input"))
    )
    (net (code "55") (name "Net-(LED22-DO)") (class "Default")
      (node (ref "LED22") (pin "2-DOUT") (pinfunction "DO_2-DOUT") (pintype "output"))
      (node (ref "LED23") (pin "4-DIN") (pinfunction "DI_4-DIN") (pintype "input"))
    )
    (net (code "56") (name "Net-(LED23-DO)") (class "Default")
      (node (ref "LED23") (pin "2-DOUT") (pinfunction "DO_2-DOUT") (pintype "output"))
      (node (ref "LED24") (pin "4-DIN") (pinfunction "DI_4-DIN") (pintype "input"))
    )
    (net (code "57") (name "Net-(LED24-DO)") (class "Default")
      (node (ref "LED24") (pin "2-DOUT") (pinfunction "DO_2-DOUT") (pintype "output"))
      (node (ref "LED25") (pin "4-DIN") (pinfunction "DI_4-DIN") (pintype "input"))
    )
    (net (code "58") (name "Net-(LED25-DO)") (class "Default")
      (node (ref "LED25") (pin "2-DOUT") (pinfunction "DO_2-DOUT") (pintype "output"))
      (node (ref "LED26") (pin "4-DIN") (pinfunction "DI_4-DIN") (pintype "input"))
    )
    (net (code "59") (name "Net-(LED26-DO)") (class "Default")
      (node (ref "LED26") (pin "2-DOUT") (pinfunction "DO_2-DOUT") (pintype "output"))
      (node (ref "LED27") (pin "4-DIN") (pinfunction "DI_4-DIN") (pintype "input"))
    )
    (net (code "60") (name "Net-(LED27-DO)") (class "Default")
      (node (ref "LED27") (pin "2-DOUT") (pinfunction "DO_2-DOUT") (pintype "output"))
      (node (ref "LED28") (pin "4-DIN") (pinfunction "DI_4-DIN") (pintype "input"))
    )
    (net (code "61") (name "Net-(LED28-DO)") (class "Default")
      (node (ref "LED28") (pin "2-DOUT") (pinfunction "DO_2-DOUT") (pintype "output"))
      (node (ref "LED29") (pin "4-DIN") (pinfunction "DI_4-DIN") (pintype "input"))
    )
    (net (code "62") (name "Net-(LED29-DO)") (class "Default")
      (node (ref "LED29") (pin "2-DOUT") (pinfunction "DO_2-DOUT") (pintype "output"))
      (node (ref "LED30") (pin "4-DIN") (pinfunction "DI_4-DIN") (pintype "input"))
    )
    (net (code "63") (name "Net-(U1-COM)") (class "Default")
      (node (ref "SV2") (pin "14") (pinfunction "14_14") (pintype "passive"))
      (node (ref "U1") (pin "1") (pinfunction "COM_1") (pintype "bidirectional"))
    )
    (net (code "64") (name "Net-(U1-S0)") (class "Default")
      (node (ref "SV2") (pin "12") (pinfunction "12_12") (pintype "passive"))
      (node (ref "U1") (pin "10") (pinfunction "S0_10") (pintype "input"))
    )
    (net (code "65") (name "Net-(U1-S1)") (class "Default")
      (node (ref "SV2") (pin "10") (pinfunction "10_10") (pintype "passive"))
      (node (ref "U1") (pin "11") (pinfunction "S1_11") (pintype "input"))
    )
    (net (code "66") (name "Net-(U1-S2)") (class "Default")
      (node (ref "SV2") (pin "13") (pinfunction "13_13") (pintype "passive"))
      (node (ref "U1") (pin "14") (pinfunction "S2_14") (pintype "input"))
    )
    (net (code "67") (name "Net-(U1-S3)") (class "Default")
      (node (ref "SV2") (pin "11") (pinfunction "11_11") (pintype "passive"))
      (node (ref "U1") (pin "13") (pinfunction "S3_13") (pintype "input"))
    )
    (net (code "68") (name "Net-(U2-COM)") (class "Default")
      (node (ref "SV2") (pin "2") (pinfunction "2_2") (pintype "passive"))
      (node (ref "U2") (pin "1") (pinfunction "COM_1") (pintype "bidirectional"))
    )
    (net (code "69") (name "Net-(U2-S0)") (class "Default")
      (node (ref "SV2") (pin "1") (pinfunction "1_1") (pintype "passive"))
      (node (ref "U2") (pin "10") (pinfunction "S0_10") (pintype "input"))
    )
    (net (code "70") (name "Net-(U2-S1)") (class "Default")
      (node (ref "SV2") (pin "3") (pinfunction "3_3") (pintype "passive"))
      (node (ref "U2") (pin "11") (pinfunction "S1_11") (pintype "input"))
    )
    (net (code "71") (name "Net-(U2-S2)") (class "Default")
      (node (ref "SV2") (pin "4") (pinfunction "4_4") (pintype "passive"))
      (node (ref "U2") (pin "14") (pinfunction "S2_14") (pintype "input"))
    )
    (net (code "72") (name "Net-(U2-S3)") (class "Default")
      (node (ref "SV2") (pin "6") (pinfunction "6_6") (pintype "passive"))
      (node (ref "U2") (pin "13") (pinfunction "S3_13") (pintype "input"))
    )
    (net (code "73") (name "VCC") (class "Default")
      (node (ref "LED1") (pin "1-VDD") (pinfunction "VDD_1-VDD") (pintype "power_in"))
      (node (ref "LED10") (pin "1-VDD") (pinfunction "VDD_1-VDD") (pintype "power_in"))
      (node (ref "LED11") (pin "1-VDD") (pinfunction "VDD_1-VDD") (pintype "power_in"))
      (node (ref "LED12") (pin "1-VDD") (pinfunction "VDD_1-VDD") (pintype "power_in"))
      (node (ref "LED13") (pin "1-VDD") (pinfunction "VDD_1-VDD") (pintype "power_in"))
      (node (ref "LED14") (pin "1-VDD") (pinfunction "VDD_1-VDD") (pintype "power_in"))
      (node (ref "LED15") (pin "1-VDD") (pinfunction "VDD_1-VDD") (pintype "power_in"))
      (node (ref "LED16") (pin "1-VDD") (pinfunction "VDD_1-VDD") (pintype "power_in"))
      (node (ref "LED17") (pin "1-VDD") (pinfunction "VDD_1-VDD") (pintype "power_in"))
      (node (ref "LED18") (pin "1-VDD") (pinfunction "VDD_1-VDD") (pintype "power_in"))
      (node (ref "LED19") (pin "1-VDD") (pinfunction "VDD_1-VDD") (pintype "power_in"))
      (node (ref "LED2") (pin "1-VDD") (pinfunction "VDD_1-VDD") (pintype "power_in"))
      (node (ref "LED20") (pin "1-VDD") (pinfunction "VDD_1-VDD") (pintype "power_in"))
      (node (ref "LED21") (pin "1-VDD") (pinfunction "VDD_1-VDD") (pintype "power_in"))
      (node (ref "LED22") (pin "1-VDD") (pinfunction "VDD_1-VDD") (pintype "power_in"))
      (node (ref "LED23") (pin "1-VDD") (pinfunction "VDD_1-VDD") (pintype "power_in"))
      (node (ref "LED24") (pin "1-VDD") (pinfunction "VDD_1-VDD") (pintype "power_in"))
      (node (ref "LED25") (pin "1-VDD") (pinfunction "VDD_1-VDD") (pintype "power_in"))
      (node (ref "LED26") (pin "1-VDD") (pinfunction "VDD_1-VDD") (pintype "power_in"))
      (node (ref "LED27") (pin "1-VDD") (pinfunction "VDD_1-VDD") (pintype "power_in"))
      (node (ref "LED28") (pin "1-VDD") (pinfunction "VDD_1-VDD") (pintype "power_in"))
      (node (ref "LED29") (pin "1-VDD") (pinfunction "VDD_1-VDD") (pintype "power_in"))
      (node (ref "LED3") (pin "1-VDD") (pinfunction "VDD_1-VDD") (pintype "power_in"))
      (node (ref "LED30") (pin "1-VDD") (pinfunction "VDD_1-VDD") (pintype "power_in"))
      (node (ref "LED4") (pin "1-VDD") (pinfunction "VDD_1-VDD") (pintype "power_in"))
      (node (ref "LED5") (pin "1-VDD") (pinfunction "VDD_1-VDD") (pintype "power_in"))
      (node (ref "LED6") (pin "1-VDD") (pinfunction "VDD_1-VDD") (pintype "power_in"))
      (node (ref "LED7") (pin "1-VDD") (pinfunction "VDD_1-VDD") (pintype "power_in"))
      (node (ref "LED8") (pin "1-VDD") (pinfunction "VDD_1-VDD") (pintype "power_in"))
      (node (ref "LED9") (pin "1-VDD") (pinfunction "VDD_1-VDD") (pintype "power_in"))
      (node (ref "PT1") (pin "C") (pinfunction "C_C") (pintype "passive"))
      (node (ref "PT10") (pin "C") (pinfunction "C_C") (pintype "passive"))
      (node (ref "PT11") (pin "C") (pinfunction "C_C") (pintype "passive"))
      (node (ref "PT12") (pin "C") (pinfunction "C_C") (pintype "passive"))
      (node (ref "PT13") (pin "C") (pinfunction "C_C") (pintype "passive"))
      (node (ref "PT14") (pin "C") (pinfunction "C_C") (pintype "passive"))
      (node (ref "PT15") (pin "C") (pinfunction "C_C") (pintype "passive"))
      (node (ref "PT16") (pin "C") (pinfunction "C_C") (pintype "passive"))
      (node (ref "PT17") (pin "C") (pinfunction "C_C") (pintype "passive"))
      (node (ref "PT18") (pin "C") (pinfunction "C_C") (pintype "passive"))
      (node (ref "PT19") (pin "C") (pinfunction "C_C") (pintype "passive"))
      (node (ref "PT2") (pin "C") (pinfunction "C_C") (pintype "passive"))
      (node (ref "PT20") (pin "C") (pinfunction "C_C") (pintype "passive"))
      (node (ref "PT21") (pin "C") (pinfunction "C_C") (pintype "passive"))
      (node (ref "PT22") (pin "C") (pinfunction "C_C") (pintype "passive"))
      (node (ref "PT23") (pin "C") (pinfunction "C_C") (pintype "passive"))
      (node (ref "PT24") (pin "C") (pinfunction "C_C") (pintype "passive"))
      (node (ref "PT25") (pin "C") (pinfunction "C_C") (pintype "passive"))
      (node (ref "PT26") (pin "C") (pinfunction "C_C") (pintype "passive"))
      (node (ref "PT27") (pin "C") (pinfunction "C_C") (pintype "passive"))
      (node (ref "PT28") (pin "C") (pinfunction "C_C") (pintype "passive"))
      (node (ref "PT29") (pin "C") (pinfunction "C_C") (pintype "passive"))
      (node (ref "PT3") (pin "C") (pinfunction "C_C") (pintype "passive"))
      (node (ref "PT30") (pin "C") (pinfunction "C_C") (pintype "passive"))
      (node (ref "PT4") (pin "C") (pinfunction "C_C") (pintype "passive"))
      (node (ref "PT5") (pin "C") (pinfunction "C_C") (pintype "passive"))
      (node (ref "PT6") (pin "C") (pinfunction "C_C") (pintype "passive"))
      (node (ref "PT7") (pin "C") (pinfunction "C_C") (pintype "passive"))
      (node (ref "PT8") (pin "C") (pinfunction "C_C") (pintype "passive"))
      (node (ref "PT9") (pin "C") (pinfunction "C_C") (pintype "passive"))
      (node (ref "SV2") (pin "9") (pinfunction "9_9") (pintype "passive"))
      (node (ref "U1") (pin "24") (pinfunction "VCC_24") (pintype "bidirectional"))
      (node (ref "U2") (pin "24") (pinfunction "VCC_24") (pintype "bidirectional"))
    )
    (net (code "74") (name "unconnected-(U1-CHAN14-Pad17)") (class "Default")
      (node (ref "U1") (pin "17") (pinfunction "CHAN14_17") (pintype "bidirectional"))
    )
    (net (code "75") (name "unconnected-(U1-CHAN15-Pad16)") (class "Default")
      (node (ref "U1") (pin "16") (pinfunction "CHAN15_16") (pintype "bidirectional"))
    )
  )
)
